# touritu.net
KiCad netlist of a schematic drawn in EAGLE
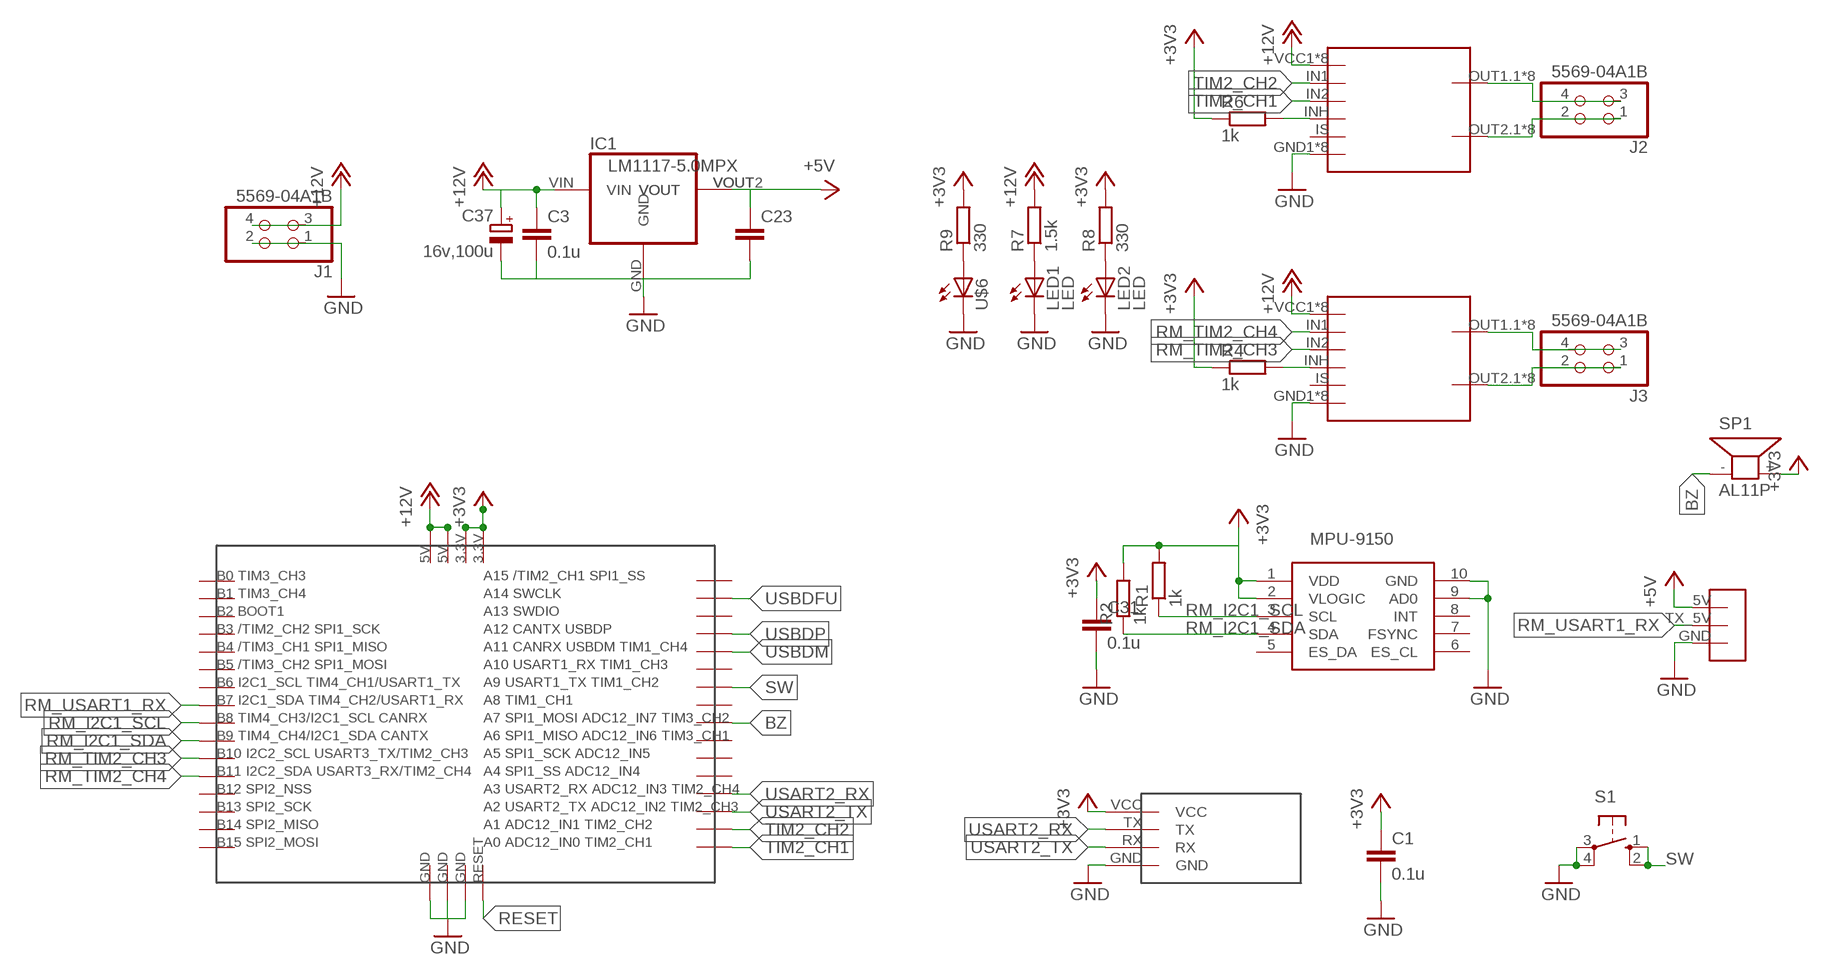
[diagram p0: schematic, sheet 1]

(export (version "E")
  (design (tool "Eeschema 10.0.6"))
  (components
    (comp (ref "C1")
      (value "0.1u")
      (footprint "eagle-import:C0603K")
      (libsource (lib "eagle-import") (part "C-EUC0603K"))
    )
    (comp (ref "C3")
      (value "0.1u")
      (footprint "eagle-import:C0603K")
      (libsource (lib "eagle-import") (part "C-EUC0603K"))
    )
    (comp (ref "C23")
      (value "C-EUC0603K")
      (footprint "eagle-import:C0603K")
      (libsource (lib "eagle-import") (part "C-EUC0603K"))
    )
    (comp (ref "C31")
      (value "0.1u")
      (footprint "eagle-import:C0603K")
      (libsource (lib "eagle-import") (part "C-EUC0603K"))
    )
    (comp (ref "C37")
      (value "16v,100u")
      (footprint "eagle-import:153CLV-0605")
      (libsource (lib "eagle-import") (part "CPOL-EU153CLV-0605"))
    )
    (comp (ref "IC1")
      (value "LM1117-5.0MPX")
      (footprint "eagle-import:SOT223")
      (libsource (lib "eagle-import") (part "LM1117IMP-5.0"))
    )
    (comp (ref "J1")
      (value "5569-04A1B")
      (footprint "eagle-import:5569-04A1_2")
      (libsource (lib "eagle-import") (part "5569-04A1B"))
    )
    (comp (ref "J2")
      (value "5569-04A1B")
      (footprint "eagle-import:5569-04A1_2")
      (libsource (lib "eagle-import") (part "5569-04A1B"))
    )
    (comp (ref "J3")
      (value "5569-04A1B")
      (footprint "eagle-import:5569-04A1_2")
      (libsource (lib "eagle-import") (part "5569-04A1B"))
    )
    (comp (ref "LED1")
      (value "LED")
      (footprint "eagle-import:T")
      (libsource (lib "eagle-import") (part "LED"))
    )
    (comp (ref "LED2")
      (value "LED")
      (footprint "eagle-import:T")
      (libsource (lib "eagle-import") (part "LED"))
    )
    (comp (ref "MPU9150")
      (value "MPU-9150")
      (footprint "eagle-import:MPU-9150")
      (libsource (lib "eagle-import") (part "MPU-9150"))
    )
    (comp (ref "R1")
      (value "1k")
      (footprint "eagle-import:R0603")
      (libsource (lib "eagle-import") (part "R-EU_R0603"))
    )
    (comp (ref "R2")
      (value "1k")
      (footprint "eagle-import:R0603")
      (libsource (lib "eagle-import") (part "R-EU_R0603"))
    )
    (comp (ref "R4")
      (value "1k")
      (footprint "eagle-import:R0603")
      (libsource (lib "eagle-import") (part "R-EU_R0603"))
    )
    (comp (ref "R6")
      (value "1k")
      (footprint "eagle-import:R0603")
      (libsource (lib "eagle-import") (part "R-EU_R0603"))
    )
    (comp (ref "R7")
      (value "1.5k")
      (footprint "eagle-import:R0603")
      (libsource (lib "eagle-import") (part "R-EU_R0603"))
    )
    (comp (ref "R8")
      (value "330")
      (footprint "eagle-import:R0603")
      (libsource (lib "eagle-import") (part "R-EU_R0603"))
    )
    (comp (ref "R9")
      (value "330")
      (footprint "eagle-import:R0603")
      (libsource (lib "eagle-import") (part "R-EU_R0603"))
    )
    (comp (ref "S1")
      (value "10-XX")
      (footprint "eagle-import:B3F-10XX")
      (fields (field (name "MPN") "B3F-1000"))
      (libsource (lib "eagle-import") (part "10-XX"))
    )
    (comp (ref "SP1")
      (value "AL11P")
      (footprint "eagle-import:AL11P")
      (libsource (lib "eagle-import") (part "AL11P"))
    )
    (comp (ref "U$1")
      (value "STBE_MINI")
      (footprint "eagle-import:STBEE_MINI")
      (libsource (lib "eagle-import") (part "STBE_MINI"))
    )
    (comp (ref "U$2")
      (value "XBEE_2.54")
      (footprint "eagle-import:XBEE_2.54")
      (libsource (lib "eagle-import") (part "XBEE_2.54"))
    )
    (comp (ref "U$4")
      (value "BTM7752")
      (footprint "eagle-import:BTM7752")
      (libsource (lib "eagle-import") (part "BTM7752"))
    )
    (comp (ref "U$6")
      (value "0603")
      (footprint "eagle-import:0603")
      (libsource (lib "eagle-import") (part "0603"))
    )
    (comp (ref "U$7")
      (value "SBDBT_5V")
      (footprint "eagle-import:SBDBT_5V")
      (libsource (lib "eagle-import") (part "SBDBT_5V"))
    )
    (comp (ref "U$9")
      (value "BTM7752")
      (footprint "eagle-import:BTM7752")
      (libsource (lib "eagle-import") (part "BTM7752"))
    )
  )
  (nets
    (net (code "1") (name "+3V3") (class "Default")
      (node (ref "C1") (pin "1") (pinfunction "1_1") (pintype "passive"))
      (node (ref "C31") (pin "1") (pinfunction "1_1") (pintype "passive"))
      (node (ref "MPU9150") (pin "1") (pinfunction "VDD_1") (pintype "bidirectional"))
      (node (ref "MPU9150") (pin "2") (pinfunction "VLOGIC_2") (pintype "bidirectional"))
      (node (ref "R1") (pin "2") (pinfunction "2_2") (pintype "passive"))
      (node (ref "R2") (pin "2") (pinfunction "2_2") (pintype "passive"))
      (node (ref "R4") (pin "1") (pinfunction "1_1") (pintype "passive"))
      (node (ref "R6") (pin "1") (pinfunction "1_1") (pintype "passive"))
      (node (ref "R8") (pin "2") (pinfunction "2_2") (pintype "passive"))
      (node (ref "R9") (pin "2") (pinfunction "2_2") (pintype "passive"))
      (node (ref "SP1") (pin "+") (pinfunction "2_+") (pintype "passive"))
      (node (ref "U$1") (pin "3.3V1") (pinfunction "3.3V1_3.3V1") (pintype "bidirectional"))
      (node (ref "U$1") (pin "3.3V2") (pinfunction "3.3V2_3.3V2") (pintype "bidirectional"))
      (node (ref "U$2") (pin "VCC") (pinfunction "VCC_VCC") (pintype "bidirectional"))
    )
    (net (code "2") (name "+5V") (class "Default")
      (node (ref "C23") (pin "1") (pinfunction "1_1") (pintype "passive"))
      (node (ref "IC1") (pin "VOUT") (pinfunction "VOUT_VOUT") (pintype "output"))
      (node (ref "IC1") (pin "VOUT2") (pinfunction "VOUT_VOUT2") (pintype "output"))
      (node (ref "U$7") (pin "5V") (pinfunction "5V_5V") (pintype "bidirectional"))
    )
    (net (code "3") (name "+12V") (class "Default")
      (node (ref "C3") (pin "1") (pinfunction "1_1") (pintype "passive"))
      (node (ref "C37") (pin "+") (pinfunction "+_+") (pintype "passive"))
      (node (ref "IC1") (pin "VIN") (pinfunction "VIN_VIN") (pintype "input"))
      (node (ref "J1") (pin "3") (pinfunction "3_3") (pintype "passive"))
      (node (ref "J1") (pin "4") (pinfunction "4_4") (pintype "passive"))
      (node (ref "R7") (pin "2") (pinfunction "2_2") (pintype "passive"))
      (node (ref "U$1") (pin "5V1") (pinfunction "5V1_5V1") (pintype "bidirectional"))
      (node (ref "U$1") (pin "5V2") (pinfunction "5V2_5V2") (pintype "bidirectional"))
      (node (ref "U$4") (pin "VCC1") (pinfunction "VCC_VCC1") (pintype "bidirectional"))
      (node (ref "U$4") (pin "VCC2") (pinfunction "VCC_VCC2") (pintype "bidirectional"))
      (node (ref "U$4") (pin "VCC3") (pinfunction "VCC_VCC3") (pintype "bidirectional"))
      (node (ref "U$4") (pin "VCC4") (pinfunction "VCC_VCC4") (pintype "bidirectional"))
      (node (ref "U$4") (pin "VCC5") (pinfunction "VCC_VCC5") (pintype "bidirectional"))
      (node (ref "U$4") (pin "VCC6") (pinfunction "VCC_VCC6") (pintype "bidirectional"))
      (node (ref "U$4") (pin "VCC7") (pinfunction "VCC_VCC7") (pintype "bidirectional"))
      (node (ref "U$4") (pin "VCC8") (pinfunction "VCC_VCC8") (pintype "bidirectional"))
      (node (ref "U$9") (pin "VCC1") (pinfunction "VCC_VCC1") (pintype "bidirectional"))
      (node (ref "U$9") (pin "VCC2") (pinfunction "VCC_VCC2") (pintype "bidirectional"))
      (node (ref "U$9") (pin "VCC3") (pinfunction "VCC_VCC3") (pintype "bidirectional"))
      (node (ref "U$9") (pin "VCC4") (pinfunction "VCC_VCC4") (pintype "bidirectional"))
      (node (ref "U$9") (pin "VCC5") (pinfunction "VCC_VCC5") (pintype "bidirectional"))
      (node (ref "U$9") (pin "VCC6") (pinfunction "VCC_VCC6") (pintype "bidirectional"))
      (node (ref "U$9") (pin "VCC7") (pinfunction "VCC_VCC7") (pintype "bidirectional"))
      (node (ref "U$9") (pin "VCC8") (pinfunction "VCC_VCC8") (pintype "bidirectional"))
    )
    (net (code "4") (name "BZ") (class "Default")
      (node (ref "SP1") (pin "-") (pinfunction "1_-") (pintype "passive"))
      (node (ref "U$1") (pin "A7") (pinfunction "A7_A7") (pintype "bidirectional"))
    )
    (net (code "5") (name "GND") (class "Default")
      (node (ref "C1") (pin "2") (pinfunction "2_2") (pintype "passive"))
      (node (ref "C23") (pin "2") (pinfunction "2_2") (pintype "passive"))
      (node (ref "C3") (pin "2") (pinfunction "2_2") (pintype "passive"))
      (node (ref "C31") (pin "2") (pinfunction "2_2") (pintype "passive"))
      (node (ref "C37") (pin "-") (pinfunction "-_-") (pintype "passive"))
      (node (ref "IC1") (pin "GND") (pinfunction "GND_GND") (pintype "power_in"))
      (node (ref "J1") (pin "1") (pinfunction "1_1") (pintype "passive"))
      (node (ref "J1") (pin "2") (pinfunction "2_2") (pintype "passive"))
      (node (ref "LED1") (pin "P$2") (pinfunction "C_P$2") (pintype "passive"))
      (node (ref "LED2") (pin "P$2") (pinfunction "C_P$2") (pintype "passive"))
      (node (ref "MPU9150") (pin "10") (pinfunction "GND_10") (pintype "bidirectional"))
      (node (ref "MPU9150") (pin "9") (pinfunction "AD0_9") (pintype "bidirectional"))
      (node (ref "S1") (pin "3") (pinfunction "P_3") (pintype "passive"))
      (node (ref "S1") (pin "4") (pinfunction "P1_4") (pintype "passive"))
      (node (ref "U$1") (pin "GND1") (pinfunction "GND1_GND1") (pintype "bidirectional"))
      (node (ref "U$1") (pin "GND2") (pinfunction "GND2_GND2") (pintype "bidirectional"))
      (node (ref "U$1") (pin "GND3") (pinfunction "GND3_GND3") (pintype "bidirectional"))
      (node (ref "U$2") (pin "GND") (pinfunction "GND_GND") (pintype "bidirectional"))
      (node (ref "U$4") (pin "GND1") (pinfunction "GND_GND1") (pintype "bidirectional"))
      (node (ref "U$4") (pin "GND2") (pinfunction "GND_GND2") (pintype "bidirectional"))
      (node (ref "U$4") (pin "GND3") (pinfunction "GND_GND3") (pintype "bidirectional"))
      (node (ref "U$4") (pin "GND4") (pinfunction "GND_GND4") (pintype "bidirectional"))
      (node (ref "U$4") (pin "GND5") (pinfunction "GND_GND5") (pintype "bidirectional"))
      (node (ref "U$4") (pin "GND6") (pinfunction "GND_GND6") (pintype "bidirectional"))
      (node (ref "U$4") (pin "GND7") (pinfunction "GND_GND7") (pintype "bidirectional"))
      (node (ref "U$4") (pin "GND8") (pinfunction "GND_GND8") (pintype "bidirectional"))
      (node (ref "U$6") (pin "C") (pinfunction "C_C") (pintype "passive"))
      (node (ref "U$7") (pin "GND") (pinfunction "GND_GND") (pintype "bidirectional"))
      (node (ref "U$9") (pin "GND1") (pinfunction "GND_GND1") (pintype "bidirectional"))
      (node (ref "U$9") (pin "GND2") (pinfunction "GND_GND2") (pintype "bidirectional"))
      (node (ref "U$9") (pin "GND3") (pinfunction "GND_GND3") (pintype "bidirectional"))
      (node (ref "U$9") (pin "GND4") (pinfunction "GND_GND4") (pintype "bidirectional"))
      (node (ref "U$9") (pin "GND5") (pinfunction "GND_GND5") (pintype "bidirectional"))
      (node (ref "U$9") (pin "GND6") (pinfunction "GND_GND6") (pintype "bidirectional"))
      (node (ref "U$9") (pin "GND7") (pinfunction "GND_GND7") (pintype "bidirectional"))
      (node (ref "U$9") (pin "GND8") (pinfunction "GND_GND8") (pintype "bidirectional"))
    )
    (net (code "6") (name "Net-(J2-Pad1)") (class "Default")
      (node (ref "J2") (pin "1") (pinfunction "1_1") (pintype "passive"))
      (node (ref "J2") (pin "2") (pinfunction "2_2") (pintype "passive"))
      (node (ref "U$4") (pin "OUT2.1") (pinfunction "OUT2_OUT2.1") (pintype "bidirectional"))
      (node (ref "U$4") (pin "OUT2.2") (pinfunction "OUT2_OUT2.2") (pintype "bidirectional"))
      (node (ref "U$4") (pin "OUT2.3") (pinfunction "OUT2_OUT2.3") (pintype "bidirectional"))
      (node (ref "U$4") (pin "OUT2.4") (pinfunction "OUT2_OUT2.4") (pintype "bidirectional"))
      (node (ref "U$4") (pin "OUT2.5") (pinfunction "OUT2_OUT2.5") (pintype "bidirectional"))
      (node (ref "U$4") (pin "OUT2.6") (pinfunction "OUT2_OUT2.6") (pintype "bidirectional"))
      (node (ref "U$4") (pin "OUT2.7") (pinfunction "OUT2_OUT2.7") (pintype "bidirectional"))
      (node (ref "U$4") (pin "OUT2.8") (pinfunction "OUT2_OUT2.8") (pintype "bidirectional"))
    )
    (net (code "7") (name "Net-(J2-Pad3)") (class "Default")
      (node (ref "J2") (pin "3") (pinfunction "3_3") (pintype "passive"))
      (node (ref "J2") (pin "4") (pinfunction "4_4") (pintype "passive"))
      (node (ref "U$4") (pin "OUT1.1") (pinfunction "OUT1_OUT1.1") (pintype "bidirectional"))
      (node (ref "U$4") (pin "OUT1.2") (pinfunction "OUT1_OUT1.2") (pintype "bidirectional"))
      (node (ref "U$4") (pin "OUT1.3") (pinfunction "OUT1_OUT1.3") (pintype "bidirectional"))
      (node (ref "U$4") (pin "OUT1.4") (pinfunction "OUT1_OUT1.4") (pintype "bidirectional"))
      (node (ref "U$4") (pin "OUT1.5") (pinfunction "OUT1_OUT1.5") (pintype "bidirectional"))
      (node (ref "U$4") (pin "OUT1.6") (pinfunction "OUT1_OUT1.6") (pintype "bidirectional"))
      (node (ref "U$4") (pin "OUT1.7") (pinfunction "OUT1_OUT1.7") (pintype "bidirectional"))
      (node (ref "U$4") (pin "OUT1.8") (pinfunction "OUT1_OUT1.8") (pintype "bidirectional"))
    )
    (net (code "8") (name "Net-(J3-Pad1)") (class "Default")
      (node (ref "J3") (pin "1") (pinfunction "1_1") (pintype "passive"))
      (node (ref "J3") (pin "2") (pinfunction "2_2") (pintype "passive"))
      (node (ref "U$9") (pin "OUT2.1") (pinfunction "OUT2_OUT2.1") (pintype "bidirectional"))
      (node (ref "U$9") (pin "OUT2.2") (pinfunction "OUT2_OUT2.2") (pintype "bidirectional"))
      (node (ref "U$9") (pin "OUT2.3") (pinfunction "OUT2_OUT2.3") (pintype "bidirectional"))
      (node (ref "U$9") (pin "OUT2.4") (pinfunction "OUT2_OUT2.4") (pintype "bidirectional"))
      (node (ref "U$9") (pin "OUT2.5") (pinfunction "OUT2_OUT2.5") (pintype "bidirectional"))
      (node (ref "U$9") (pin "OUT2.6") (pinfunction "OUT2_OUT2.6") (pintype "bidirectional"))
      (node (ref "U$9") (pin "OUT2.7") (pinfunction "OUT2_OUT2.7") (pintype "bidirectional"))
      (node (ref "U$9") (pin "OUT2.8") (pinfunction "OUT2_OUT2.8") (pintype "bidirectional"))
    )
    (net (code "9") (name "Net-(J3-Pad3)") (class "Default")
      (node (ref "J3") (pin "3") (pinfunction "3_3") (pintype "passive"))
      (node (ref "J3") (pin "4") (pinfunction "4_4") (pintype "passive"))
      (node (ref "U$9") (pin "OUT1.1") (pinfunction "OUT1_OUT1.1") (pintype "bidirectional"))
      (node (ref "U$9") (pin "OUT1.2") (pinfunction "OUT1_OUT1.2") (pintype "bidirectional"))
      (node (ref "U$9") (pin "OUT1.3") (pinfunction "OUT1_OUT1.3") (pintype "bidirectional"))
      (node (ref "U$9") (pin "OUT1.4") (pinfunction "OUT1_OUT1.4") (pintype "bidirectional"))
      (node (ref "U$9") (pin "OUT1.5") (pinfunction "OUT1_OUT1.5") (pintype "bidirectional"))
      (node (ref "U$9") (pin "OUT1.6") (pinfunction "OUT1_OUT1.6") (pintype "bidirectional"))
      (node (ref "U$9") (pin "OUT1.7") (pinfunction "OUT1_OUT1.7") (pintype "bidirectional"))
      (node (ref "U$9") (pin "OUT1.8") (pinfunction "OUT1_OUT1.8") (pintype "bidirectional"))
    )
    (net (code "10") (name "Net-(LED1-A)") (class "Default")
      (node (ref "LED1") (pin "P$1") (pinfunction "A_P$1") (pintype "passive"))
      (node (ref "R7") (pin "1") (pinfunction "1_1") (pintype "passive"))
    )
    (net (code "11") (name "Net-(LED2-A)") (class "Default")
      (node (ref "LED2") (pin "P$1") (pinfunction "A_P$1") (pintype "passive"))
      (node (ref "R8") (pin "1") (pinfunction "1_1") (pintype "passive"))
    )
    (net (code "12") (name "Net-(R4-Pad2)") (class "Default")
      (node (ref "R4") (pin "2") (pinfunction "2_2") (pintype "passive"))
      (node (ref "U$9") (pin "INH") (pinfunction "INH_INH") (pintype "bidirectional"))
    )
    (net (code "13") (name "Net-(R6-Pad2)") (class "Default")
      (node (ref "R6") (pin "2") (pinfunction "2_2") (pintype "passive"))
      (node (ref "U$4") (pin "INH") (pinfunction "INH_INH") (pintype "bidirectional"))
    )
    (net (code "14") (name "Net-(R9-Pad1)") (class "Default")
      (node (ref "R9") (pin "1") (pinfunction "1_1") (pintype "passive"))
      (node (ref "U$6") (pin "A") (pinfunction "A_A") (pintype "passive"))
    )
    (net (code "15") (name "RESET") (class "Default")
      (node (ref "U$1") (pin "RESET") (pinfunction "RESET_RESET") (pintype "bidirectional"))
    )
    (net (code "16") (name "RM_I2C1_SCL") (class "Default")
      (node (ref "MPU9150") (pin "3") (pinfunction "SCL_3") (pintype "bidirectional"))
      (node (ref "R1") (pin "1") (pinfunction "1_1") (pintype "passive"))
      (node (ref "U$1") (pin "B8") (pinfunction "B8_B8") (pintype "bidirectional"))
    )
    (net (code "17") (name "RM_I2C1_SDA") (class "Default")
      (node (ref "MPU9150") (pin "4") (pinfunction "SDA_4") (pintype "bidirectional"))
      (node (ref "R2") (pin "1") (pinfunction "1_1") (pintype "passive"))
      (node (ref "U$1") (pin "B9") (pinfunction "B9_B9") (pintype "bidirectional"))
    )
    (net (code "18") (name "RM_TIM2_CH3") (class "Default")
      (node (ref "U$1") (pin "B10") (pinfunction "B10_B10") (pintype "bidirectional"))
      (node (ref "U$9") (pin "IN2") (pinfunction "IN2_IN2") (pintype "bidirectional"))
    )
    (net (code "19") (name "RM_TIM2_CH4") (class "Default")
      (node (ref "U$1") (pin "B11") (pinfunction "B11_B11") (pintype "bidirectional"))
      (node (ref "U$9") (pin "IN1") (pinfunction "IN1_IN1") (pintype "bidirectional"))
    )
    (net (code "20") (name "RM_USART1_RX") (class "Default")
      (node (ref "U$1") (pin "B7") (pinfunction "B7_B7") (pintype "bidirectional"))
      (node (ref "U$7") (pin "TX_5V") (pinfunction "TX_5V_TX_5V") (pintype "bidirectional"))
    )
    (net (code "21") (name "SW") (class "Default")
      (node (ref "S1") (pin "1") (pinfunction "S_1") (pintype "passive"))
      (node (ref "S1") (pin "2") (pinfunction "S1_2") (pintype "passive"))
      (node (ref "U$1") (pin "A9") (pinfunction "A9_A9") (pintype "bidirectional"))
    )
    (net (code "22") (name "TIM2_CH1") (class "Default")
      (node (ref "U$1") (pin "A0") (pinfunction "A0_A0") (pintype "bidirectional"))
      (node (ref "U$4") (pin "IN2") (pinfunction "IN2_IN2") (pintype "bidirectional"))
    )
    (net (code "23") (name "TIM2_CH2") (class "Default")
      (node (ref "U$1") (pin "A1") (pinfunction "A1_A1") (pintype "bidirectional"))
      (node (ref "U$4") (pin "IN1") (pinfunction "IN1_IN1") (pintype "bidirectional"))
    )
    (net (code "24") (name "USART2_RX") (class "Default")
      (node (ref "U$1") (pin "A3") (pinfunction "A3_A3") (pintype "bidirectional"))
      (node (ref "U$2") (pin "TX") (pinfunction "TX_TX") (pintype "bidirectional"))
    )
    (net (code "25") (name "USART2_TX") (class "Default")
      (node (ref "U$1") (pin "A2") (pinfunction "A2_A2") (pintype "bidirectional"))
      (node (ref "U$2") (pin "RX") (pinfunction "RX_RX") (pintype "bidirectional"))
    )
    (net (code "26") (name "USBDFU") (class "Default")
      (node (ref "U$1") (pin "A14") (pinfunction "A14_A14") (pintype "bidirectional"))
    )
    (net (code "27") (name "USBDM") (class "Default")
      (node (ref "U$1") (pin "A11") (pinfunction "A11_A11") (pintype "bidirectional"))
    )
    (net (code "28") (name "USBDP") (class "Default")
      (node (ref "U$1") (pin "A12") (pinfunction "A12_A12") (pintype "bidirectional"))
    )
    (net (code "29") (name "unconnected-(MPU9150-ES_CL-Pad6)") (class "Default")
      (node (ref "MPU9150") (pin "6") (pinfunction "ES_CL_6") (pintype "bidirectional"))
    )
    (net (code "30") (name "unconnected-(MPU9150-ES_DA-Pad5)") (class "Default")
      (node (ref "MPU9150") (pin "5") (pinfunction "ES_DA_5") (pintype "bidirectional"))
    )
    (net (code "31") (name "unconnected-(MPU9150-FSYNC-Pad7)") (class "Default")
      (node (ref "MPU9150") (pin "7") (pinfunction "FSYNC_7") (pintype "bidirectional"))
    )
    (net (code "32") (name "unconnected-(MPU9150-INT-Pad8)") (class "Default")
      (node (ref "MPU9150") (pin "8") (pinfunction "INT_8") (pintype "bidirectional"))
    )
    (net (code "33") (name "unconnected-(U$1-PadA4)") (class "Default")
      (node (ref "U$1") (pin "A4") (pinfunction "A4_A4") (pintype "bidirectional"))
    )
    (net (code "34") (name "unconnected-(U$1-PadA5)") (class "Default")
      (node (ref "U$1") (pin "A5") (pinfunction "A5_A5") (pintype "bidirectional"))
    )
    (net (code "35") (name "unconnected-(U$1-PadA6)") (class "Default")
      (node (ref "U$1") (pin "A6") (pinfunction "A6_A6") (pintype "bidirectional"))
    )
    (net (code "36") (name "unconnected-(U$1-PadA8)") (class "Default")
      (node (ref "U$1") (pin "A8") (pinfunction "A8_A8") (pintype "bidirectional"))
    )
    (net (code "37") (name "unconnected-(U$1-PadA10)") (class "Default")
      (node (ref "U$1") (pin "A10") (pinfunction "A10_A10") (pintype "bidirectional"))
    )
    (net (code "38") (name "unconnected-(U$1-PadA13)") (class "Default")
      (node (ref "U$1") (pin "A13") (pinfunction "A13_A13") (pintype "bidirectional"))
    )
    (net (code "39") (name "unconnected-(U$1-PadA15)") (class "Default")
      (node (ref "U$1") (pin "A15") (pinfunction "A15_A15") (pintype "bidirectional"))
    )
    (net (code "40") (name "unconnected-(U$1-PadB0)") (class "Default")
      (node (ref "U$1") (pin "B0") (pinfunction "B0_B0") (pintype "bidirectional"))
    )
    (net (code "41") (name "unconnected-(U$1-PadB1)") (class "Default")
      (node (ref "U$1") (pin "B1") (pinfunction "B1_B1") (pintype "bidirectional"))
    )
    (net (code "42") (name "unconnected-(U$1-PadB2)") (class "Default")
      (node (ref "U$1") (pin "B2") (pinfunction "B2_B2") (pintype "bidirectional"))
    )
    (net (code "43") (name "unconnected-(U$1-PadB3)") (class "Default")
      (node (ref "U$1") (pin "B3") (pinfunction "B3_B3") (pintype "bidirectional"))
    )
    (net (code "44") (name "unconnected-(U$1-PadB4)") (class "Default")
      (node (ref "U$1") (pin "B4") (pinfunction "B4_B4") (pintype "bidirectional"))
    )
    (net (code "45") (name "unconnected-(U$1-PadB5)") (class "Default")
      (node (ref "U$1") (pin "B5") (pinfunction "B5_B5") (pintype "bidirectional"))
    )
    (net (code "46") (name "unconnected-(U$1-PadB6)") (class "Default")
      (node (ref "U$1") (pin "B6") (pinfunction "B6_B6") (pintype "bidirectional"))
    )
    (net (code "47") (name "unconnected-(U$1-PadB12)") (class "Default")
      (node (ref "U$1") (pin "B12") (pinfunction "B12_B12") (pintype "bidirectional"))
    )
    (net (code "48") (name "unconnected-(U$1-PadB13)") (class "Default")
      (node (ref "U$1") (pin "B13") (pinfunction "B13_B13") (pintype "bidirectional"))
    )
    (net (code "49") (name "unconnected-(U$1-PadB14)") (class "Default")
      (node (ref "U$1") (pin "B14") (pinfunction "B14_B14") (pintype "bidirectional"))
    )
    (net (code "50") (name "unconnected-(U$1-PadB15)") (class "Default")
      (node (ref "U$1") (pin "B15") (pinfunction "B15_B15") (pintype "bidirectional"))
    )
    (net (code "51") (name "unconnected-(U$4-PadIS)") (class "Default")
      (node (ref "U$4") (pin "IS") (pinfunction "IS_IS") (pintype "bidirectional"))
    )
    (net (code "52") (name "unconnected-(U$9-PadIS)") (class "Default")
      (node (ref "U$9") (pin "IS") (pinfunction "IS_IS") (pintype "bidirectional"))
    )
  )
)
